# controller-HAT.net
KiCad netlist of a schematic drawn in EAGLE
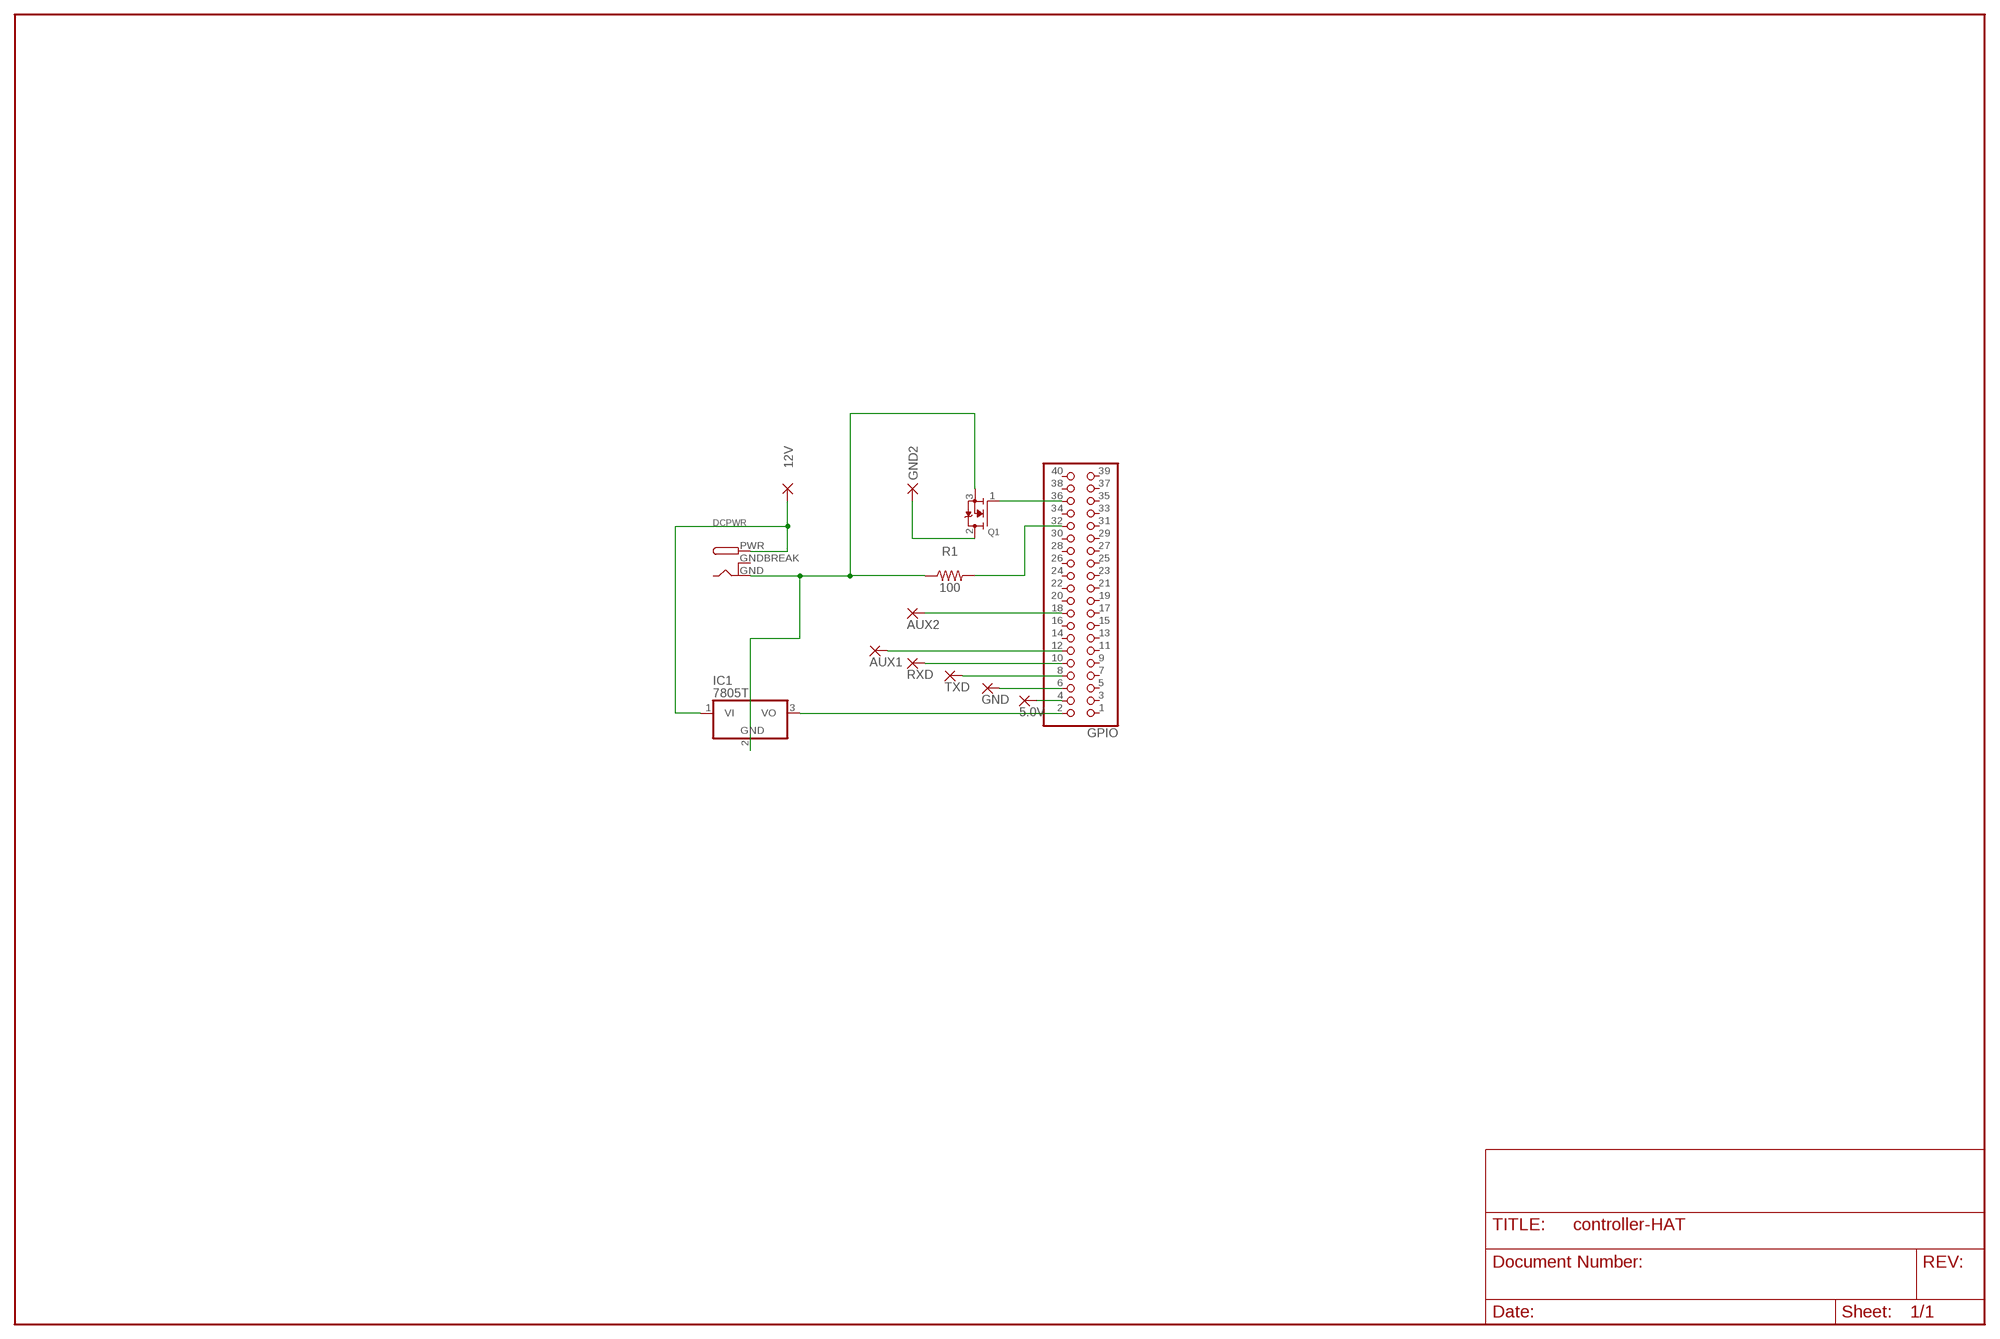
[diagram p0: schematic, sheet 1]

(export (version "E")
  (design (tool "Eeschema 10.0.6"))
  (components
    (comp (ref "5.0V")
      (value "1,6/0,9")
      (footprint "eagle-import:1,6_0,9")
      (fields (field (name "SPICEPREFIX") "X"))
      (libsource (lib "eagle-import") (part "1,6/0,9"))
    )
    (comp (ref "12V")
      (value "1,6/0,9")
      (footprint "eagle-import:1,6_0,9")
      (libsource (lib "eagle-import") (part "1,6/0,9"))
    )
    (comp (ref "AUX1")
      (value "1,6/0,9")
      (footprint "eagle-import:1,6_0,9")
      (libsource (lib "eagle-import") (part "1,6/0,9"))
    )
    (comp (ref "AUX2")
      (value "1,6/0,9")
      (footprint "eagle-import:1,6_0,9")
      (libsource (lib "eagle-import") (part "1,6/0,9"))
    )
    (comp (ref "DCPWR")
      (value "DCBARRELPTH")
      (footprint "eagle-import:DCJACK_2MM_PTH")
      (libsource (lib "eagle-import") (part "DCBARRELPTH"))
    )
    (comp (ref "GND")
      (value "1,6/0,9")
      (footprint "eagle-import:1,6_0,9")
      (libsource (lib "eagle-import") (part "1,6/0,9"))
    )
    (comp (ref "GND2")
      (value "1,6/0,9")
      (footprint "eagle-import:1,6_0,9")
      (libsource (lib "eagle-import") (part "1,6/0,9"))
    )
    (comp (ref "GPIO")
      (value "PINHD-2X20")
      (footprint "eagle-import:2X20")
      (libsource (lib "eagle-import") (part "PINHD-2X20"))
    )
    (comp (ref "IC1")
      (value "7805T")
      (footprint "eagle-import:TO220H")
      (libsource (lib "eagle-import") (part "78T05"))
    )
    (comp (ref "Q1")
      (value "MOSFET-NGDS_TO220V")
      (footprint "eagle-import:TO220V")
      (libsource (lib "eagle-import") (part "MOSFET-NGDS_TO220V"))
    )
    (comp (ref "R1")
      (value "100")
      (footprint "eagle-import:AXIAL-0.3")
      (libsource (lib "eagle-import") (part "100OHM-HORIZ-1/4W-1%"))
    )
    (comp (ref "RXD")
      (value "1,6/0,9")
      (footprint "eagle-import:1,6_0,9")
      (libsource (lib "eagle-import") (part "1,6/0,9"))
    )
    (comp (ref "TXD")
      (value "1,6/0,9")
      (footprint "eagle-import:1,6_0,9")
      (libsource (lib "eagle-import") (part "1,6/0,9"))
    )
  )
  (nets
    (net (code "1") (name "/GNDBREAK") (class "Default")
      (node (ref "DCPWR") (pin "GNDBREAK") (pinfunction "GNDBREAK_GNDBREAK") (pintype "power_in"))
    )
    (net (code "2") (name "Net-(5.0V-P)") (class "Default")
      (node (ref "5.0V") (pin "1") (pinfunction "P_1") (pintype "passive"))
      (node (ref "GPIO") (pin "4") (pinfunction "4_4") (pintype "passive"))
    )
    (net (code "3") (name "Net-(12V-P)") (class "Default")
      (node (ref "12V") (pin "1") (pinfunction "P_1") (pintype "passive"))
      (node (ref "DCPWR") (pin "PWR") (pinfunction "PWR_PWR") (pintype "power_in"))
      (node (ref "IC1") (pin "1") (pinfunction "VI_1") (pintype "input"))
    )
    (net (code "4") (name "Net-(AUX1-P)") (class "Default")
      (node (ref "AUX1") (pin "1") (pinfunction "P_1") (pintype "passive"))
      (node (ref "GPIO") (pin "12") (pinfunction "12_12") (pintype "passive"))
    )
    (net (code "5") (name "Net-(AUX2-P)") (class "Default")
      (node (ref "AUX2") (pin "1") (pinfunction "P_1") (pintype "passive"))
      (node (ref "GPIO") (pin "18") (pinfunction "18_18") (pintype "passive"))
    )
    (net (code "6") (name "Net-(GND-P)") (class "Default")
      (node (ref "GND") (pin "1") (pinfunction "P_1") (pintype "passive"))
      (node (ref "GPIO") (pin "6") (pinfunction "6_6") (pintype "passive"))
    )
    (net (code "7") (name "Net-(GND2-P)") (class "Default")
      (node (ref "GND2") (pin "1") (pinfunction "P_1") (pintype "passive"))
      (node (ref "Q1") (pin "2") (pinfunction "D_2") (pintype "bidirectional"))
    )
    (net (code "8") (name "Net-(IC1-GND)") (class "Default")
      (node (ref "DCPWR") (pin "GND") (pinfunction "GND_GND") (pintype "power_in"))
      (node (ref "IC1") (pin "2") (pinfunction "GND_2") (pintype "passive"))
      (node (ref "Q1") (pin "3") (pinfunction "S_3") (pintype "bidirectional"))
      (node (ref "R1") (pin "P$1") (pinfunction "1_P$1") (pintype "passive"))
    )
    (net (code "9") (name "Net-(IC1-VO)") (class "Default")
      (node (ref "GPIO") (pin "2") (pinfunction "2_2") (pintype "passive"))
      (node (ref "IC1") (pin "3") (pinfunction "VO_3") (pintype "passive"))
    )
    (net (code "10") (name "Net-(Q1-G)") (class "Default")
      (node (ref "GPIO") (pin "36") (pinfunction "36_36") (pintype "passive"))
      (node (ref "Q1") (pin "1") (pinfunction "G_1") (pintype "bidirectional"))
    )
    (net (code "11") (name "Net-(R1-2)") (class "Default")
      (node (ref "GPIO") (pin "32") (pinfunction "32_32") (pintype "passive"))
      (node (ref "R1") (pin "P$2") (pinfunction "2_P$2") (pintype "passive"))
    )
    (net (code "12") (name "Net-(RXD-P)") (class "Default")
      (node (ref "GPIO") (pin "10") (pinfunction "10_10") (pintype "passive"))
      (node (ref "RXD") (pin "1") (pinfunction "P_1") (pintype "passive"))
    )
    (net (code "13") (name "Net-(TXD-P)") (class "Default")
      (node (ref "GPIO") (pin "8") (pinfunction "8_8") (pintype "passive"))
      (node (ref "TXD") (pin "1") (pinfunction "P_1") (pintype "passive"))
    )
    (net (code "14") (name "unconnected-(GPIO-Pad1)") (class "Default")
      (node (ref "GPIO") (pin "1") (pinfunction "1_1") (pintype "passive"))
    )
    (net (code "15") (name "unconnected-(GPIO-Pad3)") (class "Default")
      (node (ref "GPIO") (pin "3") (pinfunction "3_3") (pintype "passive"))
    )
    (net (code "16") (name "unconnected-(GPIO-Pad5)") (class "Default")
      (node (ref "GPIO") (pin "5") (pinfunction "5_5") (pintype "passive"))
    )
    (net (code "17") (name "unconnected-(GPIO-Pad7)") (class "Default")
      (node (ref "GPIO") (pin "7") (pinfunction "7_7") (pintype "passive"))
    )
    (net (code "18") (name "unconnected-(GPIO-Pad9)") (class "Default")
      (node (ref "GPIO") (pin "9") (pinfunction "9_9") (pintype "passive"))
    )
    (net (code "19") (name "unconnected-(GPIO-Pad11)") (class "Default")
      (node (ref "GPIO") (pin "11") (pinfunction "11_11") (pintype "passive"))
    )
    (net (code "20") (name "unconnected-(GPIO-Pad13)") (class "Default")
      (node (ref "GPIO") (pin "13") (pinfunction "13_13") (pintype "passive"))
    )
    (net (code "21") (name "unconnected-(GPIO-Pad14)") (class "Default")
      (node (ref "GPIO") (pin "14") (pinfunction "14_14") (pintype "passive"))
    )
    (net (code "22") (name "unconnected-(GPIO-Pad15)") (class "Default")
      (node (ref "GPIO") (pin "15") (pinfunction "15_15") (pintype "passive"))
    )
    (net (code "23") (name "unconnected-(GPIO-Pad16)") (class "Default")
      (node (ref "GPIO") (pin "16") (pinfunction "16_16") (pintype "passive"))
    )
    (net (code "24") (name "unconnected-(GPIO-Pad17)") (class "Default")
      (node (ref "GPIO") (pin "17") (pinfunction "17_17") (pintype "passive"))
    )
    (net (code "25") (name "unconnected-(GPIO-Pad19)") (class "Default")
      (node (ref "GPIO") (pin "19") (pinfunction "19_19") (pintype "passive"))
    )
    (net (code "26") (name "unconnected-(GPIO-Pad20)") (class "Default")
      (node (ref "GPIO") (pin "20") (pinfunction "20_20") (pintype "passive"))
    )
    (net (code "27") (name "unconnected-(GPIO-Pad21)") (class "Default")
      (node (ref "GPIO") (pin "21") (pinfunction "21_21") (pintype "passive"))
    )
    (net (code "28") (name "unconnected-(GPIO-Pad22)") (class "Default")
      (node (ref "GPIO") (pin "22") (pinfunction "22_22") (pintype "passive"))
    )
    (net (code "29") (name "unconnected-(GPIO-Pad23)") (class "Default")
      (node (ref "GPIO") (pin "23") (pinfunction "23_23") (pintype "passive"))
    )
    (net (code "30") (name "unconnected-(GPIO-Pad24)") (class "Default")
      (node (ref "GPIO") (pin "24") (pinfunction "24_24") (pintype "passive"))
    )
    (net (code "31") (name "unconnected-(GPIO-Pad25)") (class "Default")
      (node (ref "GPIO") (pin "25") (pinfunction "25_25") (pintype "passive"))
    )
    (net (code "32") (name "unconnected-(GPIO-Pad26)") (class "Default")
      (node (ref "GPIO") (pin "26") (pinfunction "26_26") (pintype "passive"))
    )
    (net (code "33") (name "unconnected-(GPIO-Pad27)") (class "Default")
      (node (ref "GPIO") (pin "27") (pinfunction "27_27") (pintype "passive"))
    )
    (net (code "34") (name "unconnected-(GPIO-Pad28)") (class "Default")
      (node (ref "GPIO") (pin "28") (pinfunction "28_28") (pintype "passive"))
    )
    (net (code "35") (name "unconnected-(GPIO-Pad29)") (class "Default")
      (node (ref "GPIO") (pin "29") (pinfunction "29_29") (pintype "passive"))
    )
    (net (code "36") (name "unconnected-(GPIO-Pad30)") (class "Default")
      (node (ref "GPIO") (pin "30") (pinfunction "30_30") (pintype "passive"))
    )
    (net (code "37") (name "unconnected-(GPIO-Pad31)") (class "Default")
      (node (ref "GPIO") (pin "31") (pinfunction "31_31") (pintype "passive"))
    )
    (net (code "38") (name "unconnected-(GPIO-Pad33)") (class "Default")
      (node (ref "GPIO") (pin "33") (pinfunction "33_33") (pintype "passive"))
    )
    (net (code "39") (name "unconnected-(GPIO-Pad34)") (class "Default")
      (node (ref "GPIO") (pin "34") (pinfunction "34_34") (pintype "passive"))
    )
    (net (code "40") (name "unconnected-(GPIO-Pad35)") (class "Default")
      (node (ref "GPIO") (pin "35") (pinfunction "35_35") (pintype "passive"))
    )
    (net (code "41") (name "unconnected-(GPIO-Pad37)") (class "Default")
      (node (ref "GPIO") (pin "37") (pinfunction "37_37") (pintype "passive"))
    )
    (net (code "42") (name "unconnected-(GPIO-Pad38)") (class "Default")
      (node (ref "GPIO") (pin "38") (pinfunction "38_38") (pintype "passive"))
    )
    (net (code "43") (name "unconnected-(GPIO-Pad39)") (class "Default")
      (node (ref "GPIO") (pin "39") (pinfunction "39_39") (pintype "passive"))
    )
    (net (code "44") (name "unconnected-(GPIO-Pad40)") (class "Default")
      (node (ref "GPIO") (pin "40") (pinfunction "40_40") (pintype "passive"))
    )
  )
)
